# LightStickPower.net
KiCad netlist of a schematic drawn in EAGLE
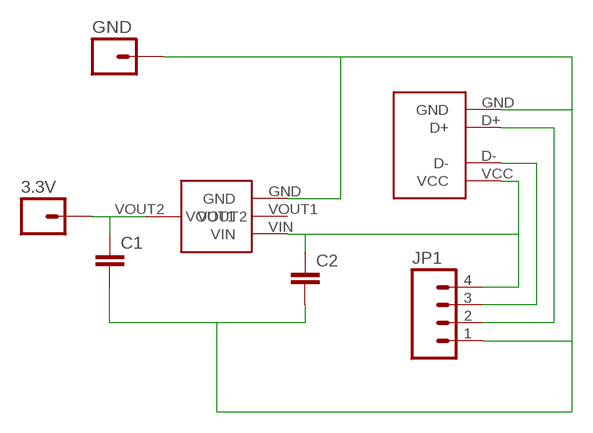
[diagram p0: schematic, sheet 1]

(export (version "E")
  (design (tool "Eeschema 10.0.6"))
  (components
    (comp (ref "3.3V")
      (value "M01PTH")
      (footprint "eagle-import:1X01")
      (libsource (lib "eagle-import") (part "M01PTH"))
    )
    (comp (ref "C1")
      (value "CAP0805")
      (footprint "eagle-import:0805")
      (libsource (lib "eagle-import") (part "CAP0805"))
    )
    (comp (ref "C2")
      (value "CAP0805")
      (footprint "eagle-import:0805")
      (libsource (lib "eagle-import") (part "CAP0805"))
    )
    (comp (ref "GND")
      (value "M01PTH")
      (footprint "eagle-import:1X01")
      (libsource (lib "eagle-import") (part "M01PTH"))
    )
    (comp (ref "JP1")
      (value "M04PTH")
      (footprint "eagle-import:1X04")
      (libsource (lib "eagle-import") (part "M04PTH"))
    )
    (comp (ref "USB1")
      (value "USB_A_932")
      (footprint "eagle-import:USB_A_932")
      (libsource (lib "eagle-import") (part "USB_A_932"))
    )
    (comp (ref "V1")
      (value "VOLTAGE_REGULATOR_AP2114H")
      (footprint "eagle-import:SOT-223")
      (libsource (lib "eagle-import") (part "VOLTAGE_REGULATOR_AP2114H"))
    )
  )
  (nets
    (net (code "1") (name "Net-(3.3V-Pad1)") (class "Default")
      (node (ref "3.3V") (pin "1") (pinfunction "1_1") (pintype "passive"))
      (node (ref "C1") (pin "1") (pinfunction "1_1") (pintype "passive"))
      (node (ref "V1") (pin "VOUT2") (pinfunction "VOUT2_VOUT2") (pintype "bidirectional"))
    )
    (net (code "2") (name "Net-(C1-Pad2)") (class "Default")
      (node (ref "C1") (pin "2") (pinfunction "2_2") (pintype "passive"))
      (node (ref "C2") (pin "2") (pinfunction "2_2") (pintype "passive"))
      (node (ref "GND") (pin "1") (pinfunction "1_1") (pintype "passive"))
      (node (ref "JP1") (pin "1") (pinfunction "1_1") (pintype "passive"))
      (node (ref "USB1") (pin "GND") (pinfunction "GND_GND") (pintype "bidirectional"))
      (node (ref "V1") (pin "GND") (pinfunction "GND_GND") (pintype "bidirectional"))
    )
    (net (code "3") (name "Net-(C2-Pad1)") (class "Default")
      (node (ref "C2") (pin "1") (pinfunction "1_1") (pintype "passive"))
      (node (ref "JP1") (pin "4") (pinfunction "4_4") (pintype "passive"))
      (node (ref "USB1") (pin "VCC") (pinfunction "VCC_VCC") (pintype "bidirectional"))
      (node (ref "V1") (pin "VIN") (pinfunction "VIN_VIN") (pintype "bidirectional"))
    )
    (net (code "4") (name "Net-(JP1-Pad2)") (class "Default")
      (node (ref "JP1") (pin "2") (pinfunction "2_2") (pintype "passive"))
      (node (ref "USB1") (pin "D+") (pinfunction "D+_D+") (pintype "bidirectional"))
    )
    (net (code "5") (name "Net-(JP1-Pad3)") (class "Default")
      (node (ref "JP1") (pin "3") (pinfunction "3_3") (pintype "passive"))
      (node (ref "USB1") (pin "D-") (pinfunction "D-_D-") (pintype "bidirectional"))
    )
    (net (code "6") (name "unconnected-(V1-PadVOUT1)") (class "Default")
      (node (ref "V1") (pin "VOUT1") (pinfunction "VOUT1_VOUT1") (pintype "bidirectional"))
    )
  )
)
